# CH32V407WEU-R0.net
KiCad netlist of a schematic drawn in Altium Designer
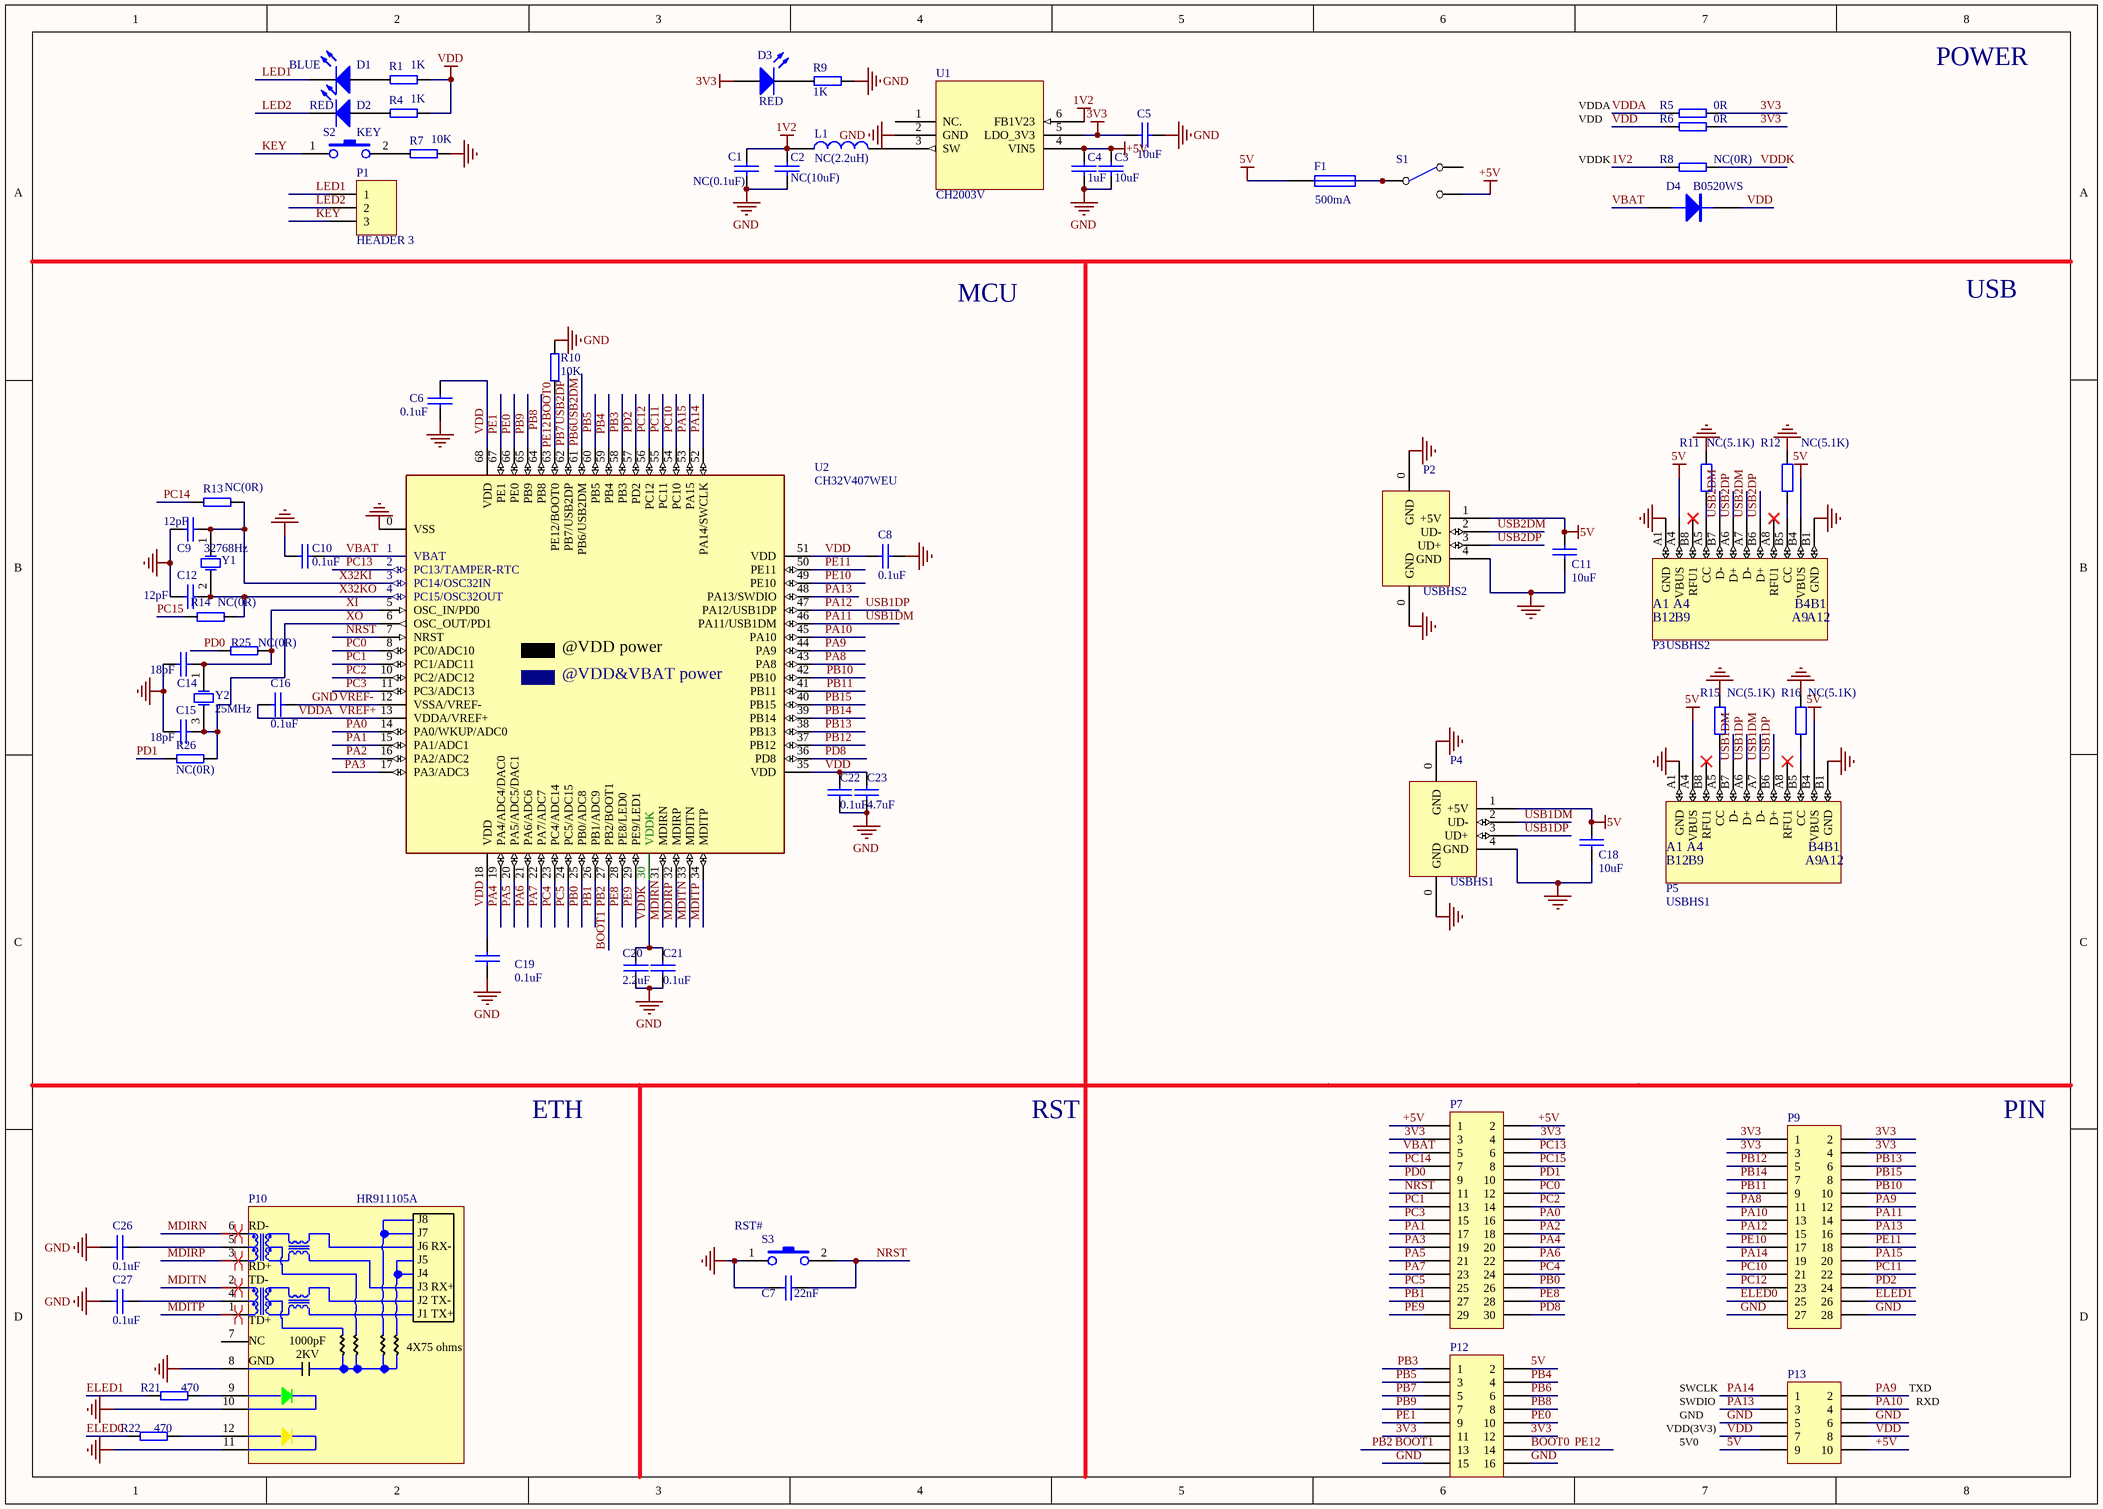
[diagram p0: CH32V407WEU-R0.SchDoc]

(export (version "E")
  (design (tool "Eeschema 10.0.6"))
  (components
    (comp (ref "C1")
      (value "NC(0.1uF)")
      (footprint "0402_C")
      (description "Capacitor")
      (libsource (lib "*") (part "CAP"))
    )
    (comp (ref "C2")
      (value "NC(10uF)")
      (footprint "0603_C")
      (description "Capacitor")
      (libsource (lib "") (part "CAP_2"))
    )
    (comp (ref "C3")
      (value "10uF")
      (footprint "0603_C")
      (description "Capacitor")
      (libsource (lib "") (part "CAP_2"))
    )
    (comp (ref "C4")
      (value "1uF")
      (footprint "0402_C")
      (description "Capacitor")
      (libsource (lib "*") (part "CAP"))
    )
    (comp (ref "C5")
      (value "10uF")
      (footprint "0603_C")
      (description "Capacitor")
      (libsource (lib "") (part "CAP_2"))
    )
    (comp (ref "C6")
      (value "0.1uF")
      (footprint "0402_C")
      (description "Capacitor")
      (libsource (lib "") (part "CAP_2"))
    )
    (comp (ref "C7")
      (value "22nF")
      (footprint "0402_C")
      (description "Capacitor")
      (libsource (lib "") (part "CAP_1"))
    )
    (comp (ref "C8")
      (value "0.1uF")
      (footprint "0402_C")
      (description "Capacitor")
      (libsource (lib "") (part "CAP_2"))
    )
    (comp (ref "C9")
      (value "12pF")
      (footprint "0402_C")
      (description "Capacitor")
      (libsource (lib "") (part "CAP_2"))
    )
    (comp (ref "C10")
      (value "0.1uF")
      (footprint "0402_C")
      (description "Capacitor")
      (libsource (lib "") (part "CAP_2"))
    )
    (comp (ref "C11")
      (value "10uF")
      (footprint "0603_C")
      (description "Capacitor")
      (libsource (lib "") (part "CAP_1"))
    )
    (comp (ref "C12")
      (value "12pF")
      (footprint "0402_C")
      (description "Capacitor")
      (libsource (lib "") (part "CAP_2"))
    )
    (comp (ref "C14")
      (value "18pF")
      (footprint "0402_C")
      (description "Capacitor")
      (libsource (lib "") (part "CAP_2"))
    )
    (comp (ref "C15")
      (value "18pF")
      (footprint "0402_C")
      (description "Capacitor")
      (libsource (lib "") (part "CAP_2"))
    )
    (comp (ref "C16")
      (value "0.1uF")
      (footprint "0402_C")
      (description "Capacitor")
      (libsource (lib "") (part "CAP_2"))
    )
    (comp (ref "C18")
      (value "10uF")
      (footprint "0603_C")
      (description "Capacitor")
      (libsource (lib "") (part "CAP_1"))
    )
    (comp (ref "C19")
      (value "0.1uF")
      (footprint "0402_C")
      (description "Capacitor")
      (libsource (lib "") (part "CAP_2"))
    )
    (comp (ref "C20")
      (value "2.2uF")
      (footprint "0402_C")
      (description "Capacitor")
      (libsource (lib "") (part "CAP_2"))
    )
    (comp (ref "C21")
      (value "0.1uF")
      (footprint "0402_C")
      (description "Capacitor")
      (libsource (lib "") (part "CAP_2"))
    )
    (comp (ref "C22")
      (value "0.1uF")
      (footprint "0402_C")
      (description "Capacitor")
      (libsource (lib "") (part "CAP_2"))
    )
    (comp (ref "C23")
      (value "4.7uF")
      (footprint "0402_C")
      (description "Capacitor")
      (libsource (lib "") (part "CAP_2"))
    )
    (comp (ref "C26")
      (value "0.1uF")
      (footprint "0402_C")
      (description "Capacitor")
      (libsource (lib "wch_sch_others") (part "CAP"))
    )
    (comp (ref "C27")
      (value "0.1uF")
      (footprint "0402_C")
      (description "Capacitor")
      (libsource (lib "wch_sch_others") (part "CAP"))
    )
    (comp (ref "D1")
      (value "BLUE")
      (footprint "0603+")
      (description "Typical INFRARED GaAs LED")
      (fields (field (name "PUBLISHER") "Altium Limited"))
      (libsource (lib "*") (part "LED0"))
    )
    (comp (ref "D2")
      (value "RED")
      (footprint "0603+")
      (description "Typical INFRARED GaAs LED")
      (fields (field (name "PUBLISHER") "Altium Limited"))
      (libsource (lib "*") (part "LED0"))
    )
    (comp (ref "D3")
      (value "RED")
      (footprint "0603+")
      (description "Typical INFRARED GaAs LED")
      (fields (field (name "PUBLISHER") "Altium Limited"))
      (libsource (lib "*") (part "LED0"))
    )
    (comp (ref "D4")
      (value "B0520WS")
      (footprint "SOD-323")
      (description "Diode")
      (libsource (lib "*") (part "DIODE"))
    )
    (comp (ref "F1")
      (value "500mA")
      (footprint "0603")
      (description "Fuse")
      (libsource (lib "wch_sch_others") (part "FUSE1"))
    )
    (comp (ref "L1") (value "NC(2.2uH)") (footprint "CD32") (libsource (lib "*") (part "INDUCTOR")))
    (comp (ref "P1")
      (value "HEADER 3")
      (footprint "SIP3-2.54MM")
      (description "Header, 3-Pin")
      (libsource (lib "wch_sch_others") (part "HEADER 3"))
    )
    (comp (ref "P2")
      (value "USBHS2")
      (footprint "USBAF")
      (description "USB Port")
      (libsource (lib "*") (part "USB"))
    )
    (comp (ref "P3")
      (value "USBHS2")
      (footprint "TYPE-C-Receptacle-2.0")
      (libsource (lib "*") (part "TYPE-C1"))
    )
    (comp (ref "P4")
      (value "USBHS1")
      (footprint "USBAF")
      (description "USB Port")
      (libsource (lib "*") (part "USB"))
    )
    (comp (ref "P5")
      (value "USBHS1")
      (footprint "TYPE-C-Receptacle-2.0")
      (libsource (lib "*") (part "TYPE-C1"))
    )
    (comp (ref "P7")
      (value "HEADER 15x2")
      (footprint "MYPCB:IDC30-2.54MM")
      (description "Header, 15-Pin, Dual row")
      (libsource (lib "wch_sch_others") (part "HEADER 15x2"))
    )
    (comp (ref "P9")
      (value "HEADER 14x2")
      (footprint "MYPCB:IDC28-2.54MM")
      (description "Header, 14-Pin, Dual row")
      (libsource (lib "wch_sch_others") (part "HEADER 14x2"))
    )
    (comp (ref "P10") (value "HR911105A") (footprint "HR911105A") (libsource (lib "*") (part "HR911105A")))
    (comp (ref "P12")
      (value "Ppin")
      (footprint "IDC16-2.54mm")
      (description "Header, 8-Pin, Dual row, Right Angle")
      (fields (field (name "PUBLISHER") "Altium Limited"))
      (libsource (lib "Miscellaneous Connectors") (part "Header 8X2H"))
    )
    (comp (ref "P13")
      (value "LINK")
      (footprint "IDC10-2.54mm")
      (description "Header, 5-Pin, Dual row, Right Angle")
      (fields (field (name "PUBLISHER") "Altium Limited"))
      (libsource (lib "Miscellaneous Connectors") (part "Header 5X2H"))
    )
    (comp (ref "R1") (value "1K") (footprint "0402") (libsource (lib "wch_sch_others") (part "RES")))
    (comp (ref "R4") (value "1K") (footprint "0402") (libsource (lib "wch_sch_others") (part "RES")))
    (comp (ref "R5") (value "0R") (footprint "0402") (libsource (lib "*") (part "R")))
    (comp (ref "R6") (value "0R") (footprint "0402") (libsource (lib "*") (part "R")))
    (comp (ref "R7") (value "10K") (footprint "0402") (libsource (lib "wch_sch_others") (part "RES")))
    (comp (ref "R8") (value "NC(0R)") (footprint "0402") (libsource (lib "*") (part "R")))
    (comp (ref "R9") (value "1K") (footprint "0402") (libsource (lib "wch_sch_others") (part "RES")))
    (comp (ref "R10") (value "10K") (footprint "0402") (libsource (lib "wch_sch_others") (part "RES")))
    (comp (ref "R11")
      (value "NC(5.1K)")
      (footprint "0402")
      (description "Resistor")
      (libsource (lib "Miscellaneous Devices") (part "Res2"))
    )
    (comp (ref "R12")
      (value "NC(5.1K)")
      (footprint "0402")
      (description "Resistor")
      (libsource (lib "Miscellaneous Devices") (part "Res2"))
    )
    (comp (ref "R13") (value "NC(0R)") (footprint "0402") (libsource (lib "wch_sch_others") (part "RES")))
    (comp (ref "R14") (value "NC(0R)") (footprint "0402") (libsource (lib "wch_sch_others") (part "RES")))
    (comp (ref "R15")
      (value "NC(5.1K)")
      (footprint "0402")
      (description "Resistor")
      (libsource (lib "Miscellaneous Devices") (part "Res2"))
    )
    (comp (ref "R16")
      (value "NC(5.1K)")
      (footprint "0402")
      (description "Resistor")
      (libsource (lib "Miscellaneous Devices") (part "Res2"))
    )
    (comp (ref "R21") (value "470") (footprint "0402") (libsource (lib "wch_sch_others") (part "RES")))
    (comp (ref "R22") (value "470") (footprint "0402") (libsource (lib "wch_sch_others") (part "RES")))
    (comp (ref "R25") (value "NC(0R)") (footprint "0402") (libsource (lib "wch_sch_others") (part "RES")))
    (comp (ref "R26") (value "NC(0R)") (footprint "0402") (libsource (lib "wch_sch_others") (part "RES")))
    (comp (ref "S1") (value "SW SPDT") (footprint "SW1") (libsource (lib "*") (part "SW SPDT")))
    (comp (ref "S2")
      (value "KEY")
      (footprint "SMD_6.1x3.65x2.5mm-KEY")
      (libsource (lib "wch_sch_others") (part "KEY1"))
    )
    (comp (ref "S3")
      (value "RST#")
      (footprint "SMD_6.1x3.65x2.5mm-KEY")
      (libsource (lib "wch_sch_others") (part "KEY1"))
    )
    (comp (ref "U1")
      (value "CH2003V")
      (footprint "SOT-23-6")
      (description "Step-Down DC-DC Converter, 5V input, 1.23V * 800mA output, with LDO 3.3V * 200mA")
      (libsource (lib "CHXXX") (part "CH2003V"))
    )
    (comp (ref "U2")
      (value "CH32V407WEU")
      (footprint "QFN68_8X8")
      (description "RISC-V FPU HD-MCU, 175MHz, USB_480M, 100M Ethernet & Phy, CAN, ADC, DAC")
      (libsource (lib "CHXXX") (part "CH32V407WEU"))
    )
    (comp (ref "Y1")
      (value "32768Hz")
      (footprint "FC-135")
      (description "Crystal Oscillator")
      (fields (field (name "PUBLISHER") "Altium Limited"))
      (libsource (lib "*") (part "XTAL"))
    )
    (comp (ref "Y2")
      (value "25MHz")
      (footprint "XT3225")
      (description "Crystal Oscillator")
      (fields (field (name "PUBLISHER") "Altium Limited"))
      (libsource (lib "") (part "XTAL_1"))
    )
  )
  (nets
    (net (code "1") (name "+5V") (class "Default")
      (node (ref "C3") (pin "2") (pinfunction "2_2") (pintype "passive"))
      (node (ref "C4") (pin "2") (pinfunction "2_2") (pintype "passive"))
      (node (ref "P13") (pin "10") (pinfunction "10_10") (pintype "passive"))
      (node (ref "P7") (pin "1") (pinfunction "1_1") (pintype "passive"))
      (node (ref "P7") (pin "2") (pinfunction "2_2") (pintype "passive"))
      (node (ref "S1") (pin "2") (pinfunction "NC_2") (pintype "passive"))
      (node (ref "U1") (pin "4") (pinfunction "VIN5_4") (pintype "power_in"))
    )
    (net (code "3") (name "/BOOT0") (class "Default")
      (node (ref "P12") (pin "14") (pinfunction "14_14") (pintype "passive"))
      (node (ref "R10") (pin "2") (pintype "passive"))
      (node (ref "U2") (pin "63") (pinfunction "PE12/BOOT0_63") (pintype "bidirectional"))
    )
    (net (code "4") (name "/BOOT1") (class "Default")
      (node (ref "P12") (pin "13") (pinfunction "13_13") (pintype "passive"))
      (node (ref "U2") (pin "27") (pinfunction "PB2/BOOT1_27") (pintype "bidirectional"))
    )
    (net (code "5") (name "/ELED0") (class "Default")
      (node (ref "P9") (pin "25") (pinfunction "25_25") (pintype "passive"))
      (node (ref "R22") (pin "1") (pintype "passive"))
    )
    (net (code "6") (name "/ELED1") (class "Default")
      (node (ref "P9") (pin "26") (pinfunction "26_26") (pintype "passive"))
      (node (ref "R21") (pin "1") (pintype "passive"))
    )
    (net (code "7") (name "/KEY") (class "Default")
      (node (ref "P1") (pin "3") (pinfunction "3_3") (pintype "passive"))
      (node (ref "S2") (pin "1") (pinfunction "1_1") (pintype "passive"))
    )
    (net (code "8") (name "/LED1") (class "Default")
      (node (ref "D1") (pin "2") (pinfunction "K_2") (pintype "passive"))
      (node (ref "P1") (pin "1") (pinfunction "1_1") (pintype "passive"))
    )
    (net (code "9") (name "/LED2") (class "Default")
      (node (ref "D2") (pin "2") (pinfunction "K_2") (pintype "passive"))
      (node (ref "P1") (pin "2") (pinfunction "2_2") (pintype "passive"))
    )
    (net (code "10") (name "/MDIRN") (class "Default")
      (node (ref "P10") (pin "6") (pintype "passive"))
      (node (ref "U2") (pin "31") (pinfunction "MDIRN_31") (pintype "bidirectional"))
    )
    (net (code "11") (name "/MDIRP") (class "Default")
      (node (ref "P10") (pin "3") (pintype "passive"))
      (node (ref "U2") (pin "32") (pinfunction "MDIRP_32") (pintype "bidirectional"))
    )
    (net (code "12") (name "/MDITN") (class "Default")
      (node (ref "P10") (pin "2") (pintype "passive"))
      (node (ref "U2") (pin "33") (pinfunction "MDITN_33") (pintype "bidirectional"))
    )
    (net (code "13") (name "/MDITP") (class "Default")
      (node (ref "P10") (pin "1") (pintype "passive"))
      (node (ref "U2") (pin "34") (pinfunction "MDITP_34") (pintype "bidirectional"))
    )
    (net (code "14") (name "/NRST") (class "Default")
      (node (ref "C7") (pin "2") (pinfunction "2_2") (pintype "passive"))
      (node (ref "P7") (pin "11") (pinfunction "11_11") (pintype "passive"))
      (node (ref "S3") (pin "2") (pinfunction "2_2") (pintype "passive"))
      (node (ref "U2") (pin "7") (pinfunction "NRST_7") (pintype "input"))
    )
    (net (code "15") (name "/PA0") (class "Default")
      (node (ref "P7") (pin "16") (pinfunction "16_16") (pintype "passive"))
      (node (ref "U2") (pin "14") (pinfunction "PA0/WKUP/ADC0_14") (pintype "bidirectional"))
    )
    (net (code "16") (name "/PA1") (class "Default")
      (node (ref "P7") (pin "17") (pinfunction "17_17") (pintype "passive"))
      (node (ref "U2") (pin "15") (pinfunction "PA1/ADC1_15") (pintype "bidirectional"))
    )
    (net (code "17") (name "/PA2") (class "Default")
      (node (ref "P7") (pin "18") (pinfunction "18_18") (pintype "passive"))
      (node (ref "U2") (pin "16") (pinfunction "PA2/ADC2_16") (pintype "bidirectional"))
    )
    (net (code "18") (name "/PA3") (class "Default")
      (node (ref "P7") (pin "19") (pinfunction "19_19") (pintype "passive"))
      (node (ref "U2") (pin "17") (pinfunction "PA3/ADC3_17") (pintype "bidirectional"))
    )
    (net (code "19") (name "/PA4") (class "Default")
      (node (ref "P7") (pin "20") (pinfunction "20_20") (pintype "passive"))
      (node (ref "U2") (pin "19") (pinfunction "PA4/ADC4/DAC0_19") (pintype "bidirectional"))
    )
    (net (code "20") (name "/PA5") (class "Default")
      (node (ref "P7") (pin "21") (pinfunction "21_21") (pintype "passive"))
      (node (ref "U2") (pin "20") (pinfunction "PA5/ADC5/DAC1_20") (pintype "bidirectional"))
    )
    (net (code "21") (name "/PA6") (class "Default")
      (node (ref "P7") (pin "22") (pinfunction "22_22") (pintype "passive"))
      (node (ref "U2") (pin "21") (pinfunction "PA6/ADC6_21") (pintype "bidirectional"))
    )
    (net (code "22") (name "/PA7") (class "Default")
      (node (ref "P7") (pin "23") (pinfunction "23_23") (pintype "passive"))
      (node (ref "U2") (pin "22") (pinfunction "PA7/ADC7_22") (pintype "bidirectional"))
    )
    (net (code "23") (name "/PA8") (class "Default")
      (node (ref "P9") (pin "11") (pinfunction "11_11") (pintype "passive"))
      (node (ref "U2") (pin "43") (pinfunction "PA8_43") (pintype "bidirectional"))
    )
    (net (code "24") (name "/PA9") (class "Default")
      (node (ref "P13") (pin "2") (pinfunction "2_2") (pintype "passive"))
      (node (ref "P9") (pin "12") (pinfunction "12_12") (pintype "passive"))
      (node (ref "U2") (pin "44") (pinfunction "PA9_44") (pintype "bidirectional"))
    )
    (net (code "25") (name "/PA10") (class "Default")
      (node (ref "P13") (pin "4") (pinfunction "4_4") (pintype "passive"))
      (node (ref "P9") (pin "13") (pinfunction "13_13") (pintype "passive"))
      (node (ref "U2") (pin "45") (pinfunction "PA10_45") (pintype "bidirectional"))
    )
    (net (code "26") (name "/PA11") (class "Default")
      (node (ref "P4") (pin "2") (pinfunction "UD-_2") (pintype "bidirectional"))
      (node (ref "P5") (pin "A7") (pinfunction "D-_A7") (pintype "bidirectional"))
      (node (ref "P5") (pin "B7") (pinfunction "D-_B7") (pintype "bidirectional"))
      (node (ref "P9") (pin "14") (pinfunction "14_14") (pintype "passive"))
      (node (ref "U2") (pin "46") (pinfunction "PA11/USB1DM_46") (pintype "bidirectional"))
    )
    (net (code "27") (name "/PA12") (class "Default")
      (node (ref "P4") (pin "3") (pinfunction "UD+_3") (pintype "bidirectional"))
      (node (ref "P5") (pin "A6") (pinfunction "D+_A6") (pintype "bidirectional"))
      (node (ref "P5") (pin "B6") (pinfunction "D+_B6") (pintype "bidirectional"))
      (node (ref "P9") (pin "15") (pinfunction "15_15") (pintype "passive"))
      (node (ref "U2") (pin "47") (pinfunction "PA12/USB1DP_47") (pintype "bidirectional"))
    )
    (net (code "28") (name "/PA13") (class "Default")
      (node (ref "P13") (pin "3") (pinfunction "3_3") (pintype "passive"))
      (node (ref "P9") (pin "16") (pinfunction "16_16") (pintype "passive"))
      (node (ref "U2") (pin "48") (pinfunction "PA13/SWDIO_48") (pintype "bidirectional"))
    )
    (net (code "29") (name "/PA14") (class "Default")
      (node (ref "P13") (pin "1") (pinfunction "1_1") (pintype "passive"))
      (node (ref "P9") (pin "19") (pinfunction "19_19") (pintype "passive"))
      (node (ref "U2") (pin "52") (pinfunction "PA14/SWCLK_52") (pintype "bidirectional"))
    )
    (net (code "30") (name "/PA15") (class "Default")
      (node (ref "P9") (pin "20") (pinfunction "20_20") (pintype "passive"))
      (node (ref "U2") (pin "53") (pinfunction "PA15_53") (pintype "bidirectional"))
    )
    (net (code "31") (name "/PB0") (class "Default")
      (node (ref "P7") (pin "26") (pinfunction "26_26") (pintype "passive"))
      (node (ref "U2") (pin "25") (pinfunction "PB0/ADC8_25") (pintype "bidirectional"))
    )
    (net (code "32") (name "/PB1") (class "Default")
      (node (ref "P7") (pin "27") (pinfunction "27_27") (pintype "passive"))
      (node (ref "U2") (pin "26") (pinfunction "PB1/ADC9_26") (pintype "bidirectional"))
    )
    (net (code "33") (name "/PB3") (class "Default")
      (node (ref "P12") (pin "1") (pinfunction "1_1") (pintype "passive"))
      (node (ref "U2") (pin "58") (pinfunction "PB3_58") (pintype "bidirectional"))
    )
    (net (code "34") (name "/PB4") (class "Default")
      (node (ref "P12") (pin "4") (pinfunction "4_4") (pintype "passive"))
      (node (ref "U2") (pin "59") (pinfunction "PB4_59") (pintype "bidirectional"))
    )
    (net (code "35") (name "/PB5") (class "Default")
      (node (ref "P12") (pin "3") (pinfunction "3_3") (pintype "passive"))
      (node (ref "U2") (pin "60") (pinfunction "PB5_60") (pintype "bidirectional"))
    )
    (net (code "36") (name "/PB6") (class "Default")
      (node (ref "P12") (pin "6") (pinfunction "6_6") (pintype "passive"))
      (node (ref "P2") (pin "2") (pinfunction "UD-_2") (pintype "bidirectional"))
      (node (ref "P3") (pin "A7") (pinfunction "D-_A7") (pintype "bidirectional"))
      (node (ref "P3") (pin "B7") (pinfunction "D-_B7") (pintype "bidirectional"))
      (node (ref "U2") (pin "61") (pinfunction "PB6/USB2DM_61") (pintype "bidirectional"))
    )
    (net (code "37") (name "/PB7") (class "Default")
      (node (ref "P12") (pin "5") (pinfunction "5_5") (pintype "passive"))
      (node (ref "P2") (pin "3") (pinfunction "UD+_3") (pintype "bidirectional"))
      (node (ref "P3") (pin "A6") (pinfunction "D+_A6") (pintype "bidirectional"))
      (node (ref "P3") (pin "B6") (pinfunction "D+_B6") (pintype "bidirectional"))
      (node (ref "U2") (pin "62") (pinfunction "PB7/USB2DP_62") (pintype "bidirectional"))
    )
    (net (code "38") (name "/PB8") (class "Default")
      (node (ref "P12") (pin "8") (pinfunction "8_8") (pintype "passive"))
      (node (ref "U2") (pin "64") (pinfunction "PB8_64") (pintype "bidirectional"))
    )
    (net (code "39") (name "/PB9") (class "Default")
      (node (ref "P12") (pin "7") (pinfunction "7_7") (pintype "passive"))
      (node (ref "U2") (pin "65") (pinfunction "PB9_65") (pintype "bidirectional"))
    )
    (net (code "40") (name "/PB10") (class "Default")
      (node (ref "P9") (pin "10") (pinfunction "10_10") (pintype "passive"))
      (node (ref "U2") (pin "42") (pinfunction "PB10_42") (pintype "bidirectional"))
    )
    (net (code "41") (name "/PB11") (class "Default")
      (node (ref "P9") (pin "9") (pinfunction "9_9") (pintype "passive"))
      (node (ref "U2") (pin "41") (pinfunction "PB11_41") (pintype "bidirectional"))
    )
    (net (code "42") (name "/PB12") (class "Default")
      (node (ref "P9") (pin "5") (pinfunction "5_5") (pintype "passive"))
      (node (ref "U2") (pin "37") (pinfunction "PB12_37") (pintype "bidirectional"))
    )
    (net (code "43") (name "/PB13") (class "Default")
      (node (ref "P9") (pin "6") (pinfunction "6_6") (pintype "passive"))
      (node (ref "U2") (pin "38") (pinfunction "PB13_38") (pintype "bidirectional"))
    )
    (net (code "44") (name "/PB14") (class "Default")
      (node (ref "P9") (pin "7") (pinfunction "7_7") (pintype "passive"))
      (node (ref "U2") (pin "39") (pinfunction "PB14_39") (pintype "bidirectional"))
    )
    (net (code "45") (name "/PB15") (class "Default")
      (node (ref "P9") (pin "8") (pinfunction "8_8") (pintype "passive"))
      (node (ref "U2") (pin "40") (pinfunction "PB15_40") (pintype "bidirectional"))
    )
    (net (code "46") (name "/PC0") (class "Default")
      (node (ref "P7") (pin "12") (pinfunction "12_12") (pintype "passive"))
      (node (ref "U2") (pin "8") (pinfunction "PC0/ADC10_8") (pintype "bidirectional"))
    )
    (net (code "47") (name "/PC1") (class "Default")
      (node (ref "P7") (pin "13") (pinfunction "13_13") (pintype "passive"))
      (node (ref "U2") (pin "9") (pinfunction "PC1/ADC11_9") (pintype "bidirectional"))
    )
    (net (code "48") (name "/PC2") (class "Default")
      (node (ref "P7") (pin "14") (pinfunction "14_14") (pintype "passive"))
      (node (ref "U2") (pin "10") (pinfunction "PC2/ADC12_10") (pintype "bidirectional"))
    )
    (net (code "49") (name "/PC3") (class "Default")
      (node (ref "P7") (pin "15") (pinfunction "15_15") (pintype "passive"))
      (node (ref "U2") (pin "11") (pinfunction "PC3/ADC13_11") (pintype "bidirectional"))
    )
    (net (code "50") (name "/PC4") (class "Default")
      (node (ref "P7") (pin "24") (pinfunction "24_24") (pintype "passive"))
      (node (ref "U2") (pin "23") (pinfunction "PC4/ADC14_23") (pintype "bidirectional"))
    )
    (net (code "51") (name "/PC5") (class "Default")
      (node (ref "P7") (pin "25") (pinfunction "25_25") (pintype "passive"))
      (node (ref "U2") (pin "24") (pinfunction "PC5/ADC15_24") (pintype "bidirectional"))
    )
    (net (code "52") (name "/PC10") (class "Default")
      (node (ref "P9") (pin "21") (pinfunction "21_21") (pintype "passive"))
      (node (ref "U2") (pin "54") (pinfunction "PC10_54") (pintype "bidirectional"))
    )
    (net (code "53") (name "/PC11") (class "Default")
      (node (ref "P9") (pin "22") (pinfunction "22_22") (pintype "passive"))
      (node (ref "U2") (pin "55") (pinfunction "PC11_55") (pintype "bidirectional"))
    )
    (net (code "54") (name "/PC12") (class "Default")
      (node (ref "P9") (pin "23") (pinfunction "23_23") (pintype "passive"))
      (node (ref "U2") (pin "56") (pinfunction "PC12_56") (pintype "bidirectional"))
    )
    (net (code "55") (name "/PC13") (class "Default")
      (node (ref "P7") (pin "6") (pinfunction "6_6") (pintype "passive"))
      (node (ref "U2") (pin "2") (pinfunction "PC13/TAMPER-RTC_2") (pintype "bidirectional"))
    )
    (net (code "56") (name "/PC14") (class "Default")
      (node (ref "P7") (pin "7") (pinfunction "7_7") (pintype "passive"))
      (node (ref "R13") (pin "1") (pintype "passive"))
    )
    (net (code "57") (name "/PC15") (class "Default")
      (node (ref "P7") (pin "8") (pinfunction "8_8") (pintype "passive"))
      (node (ref "R14") (pin "1") (pintype "passive"))
    )
    (net (code "58") (name "/PD0") (class "Default")
      (node (ref "P7") (pin "9") (pinfunction "9_9") (pintype "passive"))
      (node (ref "R25") (pin "1") (pintype "passive"))
    )
    (net (code "59") (name "/PD1") (class "Default")
      (node (ref "P7") (pin "10") (pinfunction "10_10") (pintype "passive"))
      (node (ref "R26") (pin "2") (pintype "passive"))
    )
    (net (code "60") (name "/PD2") (class "Default")
      (node (ref "P9") (pin "24") (pinfunction "24_24") (pintype "passive"))
      (node (ref "U2") (pin "57") (pinfunction "PD2_57") (pintype "bidirectional"))
    )
    (net (code "61") (name "/PD8") (class "Default")
      (node (ref "P7") (pin "30") (pinfunction "30_30") (pintype "passive"))
      (node (ref "U2") (pin "36") (pinfunction "PD8_36") (pintype "bidirectional"))
    )
    (net (code "62") (name "/PE0") (class "Default")
      (node (ref "P12") (pin "10") (pinfunction "10_10") (pintype "passive"))
      (node (ref "U2") (pin "66") (pinfunction "PE0_66") (pintype "bidirectional"))
    )
    (net (code "63") (name "/PE1") (class "Default")
      (node (ref "P12") (pin "9") (pinfunction "9_9") (pintype "passive"))
      (node (ref "U2") (pin "67") (pinfunction "PE1_67") (pintype "bidirectional"))
    )
    (net (code "64") (name "/PE8") (class "Default")
      (node (ref "P7") (pin "28") (pinfunction "28_28") (pintype "passive"))
      (node (ref "U2") (pin "28") (pinfunction "PE8/LED0_28") (pintype "bidirectional"))
    )
    (net (code "65") (name "/PE9") (class "Default")
      (node (ref "P7") (pin "29") (pinfunction "29_29") (pintype "passive"))
      (node (ref "U2") (pin "29") (pinfunction "PE9/LED1_29") (pintype "bidirectional"))
    )
    (net (code "66") (name "/PE10") (class "Default")
      (node (ref "P9") (pin "17") (pinfunction "17_17") (pintype "passive"))
      (node (ref "U2") (pin "49") (pinfunction "PE10_49") (pintype "bidirectional"))
    )
    (net (code "67") (name "/PE11") (class "Default")
      (node (ref "P9") (pin "18") (pinfunction "18_18") (pintype "passive"))
      (node (ref "U2") (pin "50") (pinfunction "PE11_50") (pintype "bidirectional"))
    )
    (net (code "68") (name "/VBAT") (class "Default")
      (node (ref "C10") (pin "2") (pinfunction "2_2") (pintype "passive"))
      (node (ref "D4") (pin "1") (pinfunction "A_1") (pintype "passive"))
      (node (ref "P7") (pin "5") (pinfunction "5_5") (pintype "passive"))
      (node (ref "U2") (pin "1") (pinfunction "VBAT_1") (pintype "power_in"))
    )
    (net (code "69") (name "/VDDA") (class "Default")
      (node (ref "C16") (pin "1") (pinfunction "1_1") (pintype "passive"))
      (node (ref "R5") (pin "2") (pinfunction "2_2") (pintype "passive"))
      (node (ref "U2") (pin "13") (pinfunction "VDDA/VREF+_13") (pintype "power_in"))
    )
    (net (code "70") (name "/VDDK") (class "Default")
      (node (ref "C20") (pin "2") (pinfunction "2_2") (pintype "passive"))
      (node (ref "C21") (pin "2") (pinfunction "2_2") (pintype "passive"))
      (node (ref "R8") (pin "1") (pinfunction "1_1") (pintype "passive"))
      (node (ref "U2") (pin "30") (pinfunction "VDDK_30") (pintype "power_in"))
    )
    (net (code "71") (name "/X32KI") (class "Default")
      (node (ref "C9") (pin "2") (pinfunction "2_2") (pintype "passive"))
      (node (ref "R13") (pin "2") (pintype "passive"))
      (node (ref "U2") (pin "3") (pinfunction "PC14/OSC32IN_3") (pintype "bidirectional"))
      (node (ref "Y1") (pin "1") (pinfunction "OSC1_1") (pintype "passive"))
    )
    (net (code "72") (name "/X32KO") (class "Default")
      (node (ref "C12") (pin "2") (pinfunction "2_2") (pintype "passive"))
      (node (ref "R14") (pin "2") (pintype "passive"))
      (node (ref "U2") (pin "4") (pinfunction "PC15/OSC32OUT_4") (pintype "bidirectional"))
      (node (ref "Y1") (pin "2") (pinfunction "OSC2_2") (pintype "passive"))
    )
    (net (code "73") (name "/XI") (class "Default")
      (node (ref "C14") (pin "2") (pinfunction "2_2") (pintype "passive"))
      (node (ref "R25") (pin "2") (pintype "passive"))
      (node (ref "U2") (pin "5") (pinfunction "OSC_IN/PD0_5") (pintype "input"))
      (node (ref "Y2") (pin "1") (pinfunction "OSC1_1") (pintype "passive"))
    )
    (net (code "74") (name "/XO") (class "Default")
      (node (ref "C15") (pin "2") (pinfunction "2_2") (pintype "passive"))
      (node (ref "R26") (pin "1") (pintype "passive"))
      (node (ref "U2") (pin "6") (pinfunction "OSC_OUT/PD1_6") (pintype "output"))
      (node (ref "Y2") (pin "3") (pinfunction "OSC2_3") (pintype "passive"))
    )
    (net (code "75") (name "1V2") (class "Default")
      (node (ref "C1") (pin "2") (pinfunction "2_2") (pintype "passive"))
      (node (ref "C2") (pin "2") (pinfunction "2_2") (pintype "passive"))
      (node (ref "L1") (pin "2") (pinfunction "2_2") (pintype "passive"))
      (node (ref "R8") (pin "2") (pinfunction "2_2") (pintype "passive"))
      (node (ref "U1") (pin "6") (pinfunction "FB1V23_6") (pintype "input"))
    )
    (net (code "76") (name "3V3") (class "Default")
      (node (ref "C5") (pin "2") (pinfunction "2_2") (pintype "passive"))
      (node (ref "D3") (pin "1") (pinfunction "A_1") (pintype "passive"))
      (node (ref "P12") (pin "11") (pinfunction "11_11") (pintype "passive"))
      (node (ref "P12") (pin "12") (pinfunction "12_12") (pintype "passive"))
      (node (ref "P7") (pin "3") (pinfunction "3_3") (pintype "passive"))
      (node (ref "P7") (pin "4") (pinfunction "4_4") (pintype "passive"))
      (node (ref "P9") (pin "1") (pinfunction "1_1") (pintype "passive"))
      (node (ref "P9") (pin "2") (pinfunction "2_2") (pintype "passive"))
      (node (ref "P9") (pin "3") (pinfunction "3_3") (pintype "passive"))
      (node (ref "P9") (pin "4") (pinfunction "4_4") (pintype "passive"))
      (node (ref "R5") (pin "1") (pinfunction "1_1") (pintype "passive"))
      (node (ref "R6") (pin "1") (pinfunction "1_1") (pintype "passive"))
      (node (ref "U1") (pin "5") (pinfunction "LDO_3V3_5") (pintype "power_in"))
    )
    (net (code "77") (name "5V") (class "Default")
      (node (ref "C11") (pin "1") (pinfunction "1_1") (pintype "passive"))
      (node (ref "C18") (pin "1") (pinfunction "1_1") (pintype "passive"))
      (node (ref "F1") (pin "1") (pinfunction "1_1") (pintype "passive"))
      (node (ref "P12") (pin "2") (pinfunction "2_2") (pintype "passive"))
      (node (ref "P13") (pin "9") (pinfunction "9_9") (pintype "passive"))
      (node (ref "P2") (pin "1") (pinfunction "+5V_1") (pintype "power_in"))
      (node (ref "P3") (pin "A4") (pinfunction "VBUS_A4") (pintype "bidirectional"))
      (node (ref "P3") (pin "B4") (pinfunction "VBUS_B4") (pintype "bidirectional"))
      (node (ref "P4") (pin "1") (pinfunction "+5V_1") (pintype "power_in"))
      (node (ref "P5") (pin "A4") (pinfunction "VBUS_A4") (pintype "bidirectional"))
      (node (ref "P5") (pin "B4") (pinfunction "VBUS_B4") (pintype "bidirectional"))
    )
    (net (code "78") (name "GND") (class "Default")
      (node (ref "C1") (pin "1") (pinfunction "1_1") (pintype "passive"))
      (node (ref "C10") (pin "1") (pinfunction "1_1") (pintype "passive"))
      (node (ref "C11") (pin "2") (pinfunction "2_2") (pintype "passive"))
      (node (ref "C12") (pin "1") (pinfunction "1_1") (pintype "passive"))
      (node (ref "C14") (pin "1") (pinfunction "1_1") (pintype "passive"))
      (node (ref "C15") (pin "1") (pinfunction "1_1") (pintype "passive"))
      (node (ref "C16") (pin "2") (pinfunction "2_2") (pintype "passive"))
      (node (ref "C18") (pin "2") (pinfunction "2_2") (pintype "passive"))
      (node (ref "C19") (pin "1") (pinfunction "1_1") (pintype "passive"))
      (node (ref "C2") (pin "1") (pinfunction "1_1") (pintype "passive"))
      (node (ref "C20") (pin "1") (pinfunction "1_1") (pintype "passive"))
      (node (ref "C21") (pin "1") (pinfunction "1_1") (pintype "passive"))
      (node (ref "C22") (pin "1") (pinfunction "1_1") (pintype "passive"))
      (node (ref "C23") (pin "1") (pinfunction "1_1") (pintype "passive"))
      (node (ref "C26") (pin "1") (pinfunction "1_1") (pintype "passive"))
      (node (ref "C27") (pin "1") (pinfunction "1_1") (pintype "passive"))
      (node (ref "C3") (pin "1") (pinfunction "1_1") (pintype "passive"))
      (node (ref "C4") (pin "1") (pinfunction "1_1") (pintype "passive"))
      (node (ref "C5") (pin "1") (pinfunction "1_1") (pintype "passive"))
      (node (ref "C6") (pin "1") (pinfunction "1_1") (pintype "passive"))
      (node (ref "C7") (pin "1") (pinfunction "1_1") (pintype "passive"))
      (node (ref "C8") (pin "2") (pinfunction "2_2") (pintype "passive"))
      (node (ref "C9") (pin "1") (pinfunction "1_1") (pintype "passive"))
      (node (ref "P10") (pin "10") (pintype "passive"))
      (node (ref "P10") (pin "11") (pintype "passive"))
      (node (ref "P10") (pin "8") (pintype "passive"))
      (node (ref "P12") (pin "15") (pinfunction "15_15") (pintype "passive"))
      (node (ref "P12") (pin "16") (pinfunction "16_16") (pintype "passive"))
      (node (ref "P13") (pin "5") (pinfunction "5_5") (pintype "passive"))
      (node (ref "P13") (pin "6") (pinfunction "6_6") (pintype "passive"))
      (node (ref "P2") (pin "0") (pinfunction "GND_0") (pintype "power_in"))
      (node (ref "P2") (pin "4") (pinfunction "GND_4") (pintype "power_in"))
      (node (ref "P3") (pin "A1") (pinfunction "GND_A1") (pintype "bidirectional"))
      (node (ref "P3") (pin "B1") (pinfunction "GND_B1") (pintype "bidirectional"))
      (node (ref "P4") (pin "0") (pinfunction "GND_0") (pintype "power_in"))
      (node (ref "P4") (pin "4") (pinfunction "GND_4") (pintype "power_in"))
      (node (ref "P5") (pin "A1") (pinfunction "GND_A1") (pintype "bidirectional"))
      (node (ref "P5") (pin "B1") (pinfunction "GND_B1") (pintype "bidirectional"))
      (node (ref "P9") (pin "27") (pinfunction "27_27") (pintype "passive"))
      (node (ref "P9") (pin "28") (pinfunction "28_28") (pintype "passive"))
      (node (ref "R10") (pin "1") (pintype "passive"))
      (node (ref "R11") (pin "2") (pinfunction "2_2") (pintype "passive"))
      (node (ref "R12") (pin "2") (pinfunction "2_2") (pintype "passive"))
      (node (ref "R15") (pin "2") (pinfunction "2_2") (pintype "passive"))
      (node (ref "R16") (pin "2") (pinfunction "2_2") (pintype "passive"))
      (node (ref "R7") (pin "1") (pintype "passive"))
      (node (ref "R9") (pin "2") (pintype "passive"))
      (node (ref "S3") (pin "1") (pinfunction "1_1") (pintype "passive"))
      (node (ref "U1") (pin "2") (pinfunction "GND_2") (pintype "power_in"))
      (node (ref "U2") (pin "0") (pinfunction "VSS_0") (pintype "power_in"))
      (node (ref "U2") (pin "12") (pinfunction "VSSA/VREF-_12") (pintype "power_in"))
    )
    (net (code "79") (name "Net-(C26-Pad2)") (class "Default")
      (node (ref "C26") (pin "2") (pinfunction "2_2") (pintype "passive"))
      (node (ref "P10") (pin "5") (pintype "passive"))
    )
    (net (code "80") (name "Net-(C27-Pad2)") (class "Default")
      (node (ref "C27") (pin "2") (pinfunction "2_2") (pintype "passive"))
      (node (ref "P10") (pin "4") (pintype "passive"))
    )
    (net (code "81") (name "Net-(D1-A)") (class "Default")
      (node (ref "D1") (pin "1") (pinfunction "A_1") (pintype "passive"))
      (node (ref "R1") (pin "2") (pintype "passive"))
    )
    (net (code "82") (name "Net-(D2-A)") (class "Default")
      (node (ref "D2") (pin "1") (pinfunction "A_1") (pintype "passive"))
      (node (ref "R4") (pin "2") (pintype "passive"))
    )
    (net (code "83") (name "Net-(D3-K)") (class "Default")
      (node (ref "D3") (pin "2") (pinfunction "K_2") (pintype "passive"))
      (node (ref "R9") (pin "1") (pintype "passive"))
    )
    (net (code "84") (name "Net-(P3-CC-PadA5)") (class "Default")
      (node (ref "P3") (pin "A5") (pinfunction "CC_A5") (pintype "bidirectional"))
      (node (ref "R11") (pin "1") (pinfunction "1_1") (pintype "passive"))
    )
    (net (code "85") (name "Net-(P3-CC-PadB5)") (class "Default")
      (node (ref "P3") (pin "B5") (pinfunction "CC_B5") (pintype "bidirectional"))
      (node (ref "R12") (pin "1") (pinfunction "1_1") (pintype "passive"))
    )
    (net (code "86") (name "Net-(P5-CC-PadA5)") (class "Default")
      (node (ref "P5") (pin "A5") (pinfunction "CC_A5") (pintype "bidirectional"))
      (node (ref "R15") (pin "1") (pinfunction "1_1") (pintype "passive"))
    )
    (net (code "87") (name "Net-(P5-CC-PadB5)") (class "Default")
      (node (ref "P5") (pin "B5") (pinfunction "CC_B5") (pintype "bidirectional"))
      (node (ref "R16") (pin "1") (pinfunction "1_1") (pintype "passive"))
    )
    (net (code "88") (name "Net-(P10-Pad9)") (class "Default")
      (node (ref "P10") (pin "9") (pintype "passive"))
      (node (ref "R21") (pin "2") (pintype "passive"))
    )
    (net (code "89") (name "Net-(P10-Pad12)") (class "Default")
      (node (ref "P10") (pin "12") (pintype "passive"))
      (node (ref "R22") (pin "2") (pintype "passive"))
    )
    (net (code "90") (name "Net-(R7-Pad2)") (class "Default")
      (node (ref "R7") (pin "2") (pintype "passive"))
      (node (ref "S2") (pin "2") (pinfunction "2_2") (pintype "passive"))
    )
    (net (code "91") (name "Net-(S1-COMMON)") (class "Default")
      (node (ref "F1") (pin "2") (pinfunction "2_2") (pintype "passive"))
      (node (ref "S1") (pin "1") (pinfunction "COMMON_1") (pintype "passive"))
    )
    (net (code "92") (name "Net-(U1-SW)") (class "Default")
      (node (ref "L1") (pin "1") (pinfunction "1_1") (pintype "passive"))
      (node (ref "U1") (pin "3") (pinfunction "SW_3") (pintype "output"))
    )
    (net (code "93") (name "VDD") (class "Default")
      (node (ref "C19") (pin "2") (pinfunction "2_2") (pintype "passive"))
      (node (ref "C22") (pin "2") (pinfunction "2_2") (pintype "passive"))
      (node (ref "C23") (pin "2") (pinfunction "2_2") (pintype "passive"))
      (node (ref "C6") (pin "2") (pinfunction "2_2") (pintype "passive"))
      (node (ref "C8") (pin "1") (pinfunction "1_1") (pintype "passive"))
      (node (ref "D4") (pin "2") (pinfunction "K_2") (pintype "passive"))
      (node (ref "P13") (pin "7") (pinfunction "7_7") (pintype "passive"))
      (node (ref "P13") (pin "8") (pinfunction "8_8") (pintype "passive"))
      (node (ref "R1") (pin "1") (pintype "passive"))
      (node (ref "R4") (pin "1") (pintype "passive"))
      (node (ref "R6") (pin "2") (pinfunction "2_2") (pintype "passive"))
      (node (ref "U2") (pin "18") (pinfunction "VDD_18") (pintype "power_in"))
      (node (ref "U2") (pin "35") (pinfunction "VDD_35") (pintype "power_in"))
      (node (ref "U2") (pin "51") (pinfunction "VDD_51") (pintype "power_in"))
      (node (ref "U2") (pin "68") (pinfunction "VDD_68") (pintype "power_in"))
    )
    (net (code "94") (name "unconnected-(P3-RFU1-PadA8)") (class "Default")
      (node (ref "P3") (pin "A8") (pinfunction "RFU1_A8") (pintype "bidirectional+no_connect"))
    )
    (net (code "95") (name "unconnected-(P3-RFU1-PadB8)") (class "Default")
      (node (ref "P3") (pin "B8") (pinfunction "RFU1_B8") (pintype "bidirectional+no_connect"))
    )
    (net (code "96") (name "unconnected-(P5-RFU1-PadA8)") (class "Default")
      (node (ref "P5") (pin "A8") (pinfunction "RFU1_A8") (pintype "bidirectional+no_connect"))
    )
    (net (code "97") (name "unconnected-(P5-RFU1-PadB8)") (class "Default")
      (node (ref "P5") (pin "B8") (pinfunction "RFU1_B8") (pintype "bidirectional+no_connect"))
    )
    (net (code "98") (name "unconnected-(P10-Pad7)") (class "Default")
      (node (ref "P10") (pin "7") (pintype "passive"))
    )
    (net (code "99") (name "unconnected-(S1-NO-Pad3)") (class "Default")
      (node (ref "S1") (pin "3") (pinfunction "NO_3") (pintype "passive"))
    )
    (net (code "100") (name "unconnected-(U1-NC.-Pad1)") (class "Default")
      (node (ref "U1") (pin "1") (pinfunction "NC._1") (pintype "passive"))
    )
  )
)
